# -.net
KiCad netlist of a schematic drawn in Altium Designer
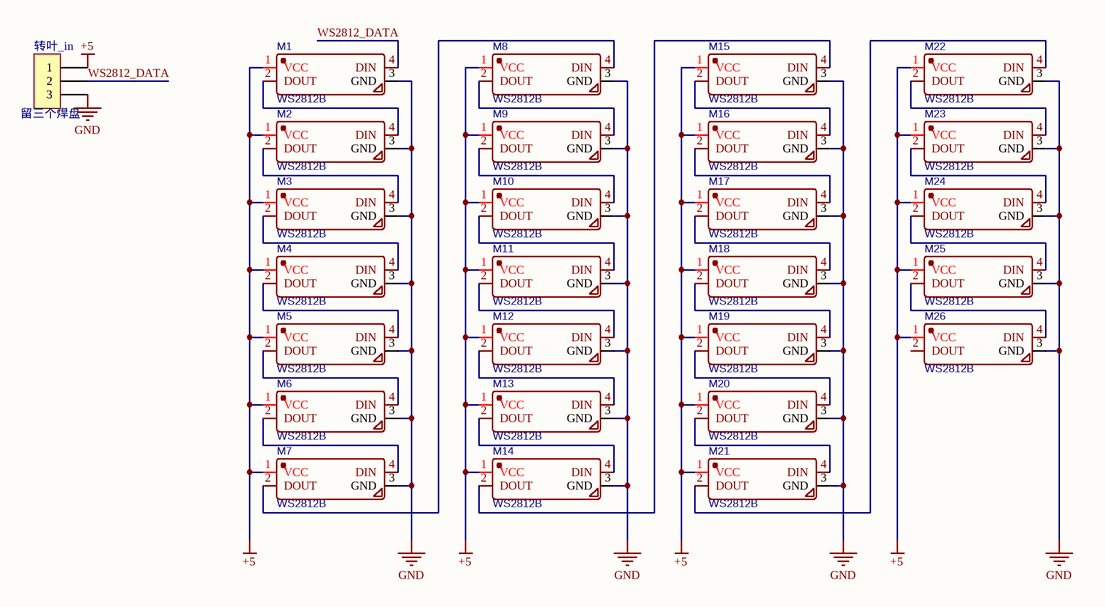
[diagram p0: 转叶板-转叶.SchDoc]

(export (version "E")
  (design (tool "Eeschema 10.0.6"))
  (components
    (comp (ref "M1")
      (value "WS2812B")
      (footprint "WS2812-NEW")
      (fields (field (name "BOM_SUPPLIER PART") "C114585") (field (name "CONTRIBUTOR") "LCSC"))
      (libsource (lib "PCB_Project") (part "WS2812B"))
    )
    (comp (ref "M2")
      (value "WS2812B")
      (footprint "WS2812-NEW")
      (fields (field (name "BOM_SUPPLIER PART") "C114585") (field (name "CONTRIBUTOR") "LCSC"))
      (libsource (lib "PCB_Project") (part "WS2812B"))
    )
    (comp (ref "M3")
      (value "WS2812B")
      (footprint "WS2812-NEW")
      (fields (field (name "BOM_SUPPLIER PART") "C114585") (field (name "CONTRIBUTOR") "LCSC"))
      (libsource (lib "PCB_Project") (part "WS2812B"))
    )
    (comp (ref "M4")
      (value "WS2812B")
      (footprint "WS2812-NEW")
      (fields (field (name "BOM_SUPPLIER PART") "C114585") (field (name "CONTRIBUTOR") "LCSC"))
      (libsource (lib "PCB_Project") (part "WS2812B"))
    )
    (comp (ref "M5")
      (value "WS2812B")
      (footprint "WS2812-NEW")
      (fields (field (name "BOM_SUPPLIER PART") "C114585") (field (name "CONTRIBUTOR") "LCSC"))
      (libsource (lib "PCB_Project") (part "WS2812B"))
    )
    (comp (ref "M6")
      (value "WS2812B")
      (footprint "WS2812-NEW")
      (fields (field (name "BOM_SUPPLIER PART") "C114585") (field (name "CONTRIBUTOR") "LCSC"))
      (libsource (lib "PCB_Project") (part "WS2812B"))
    )
    (comp (ref "M7")
      (value "WS2812B")
      (footprint "WS2812-NEW")
      (fields (field (name "BOM_SUPPLIER PART") "C114585") (field (name "CONTRIBUTOR") "LCSC"))
      (libsource (lib "PCB_Project") (part "WS2812B"))
    )
    (comp (ref "M8")
      (value "WS2812B")
      (footprint "WS2812-NEW")
      (fields (field (name "BOM_SUPPLIER PART") "C114585") (field (name "CONTRIBUTOR") "LCSC"))
      (libsource (lib "PCB_Project") (part "WS2812B"))
    )
    (comp (ref "M9")
      (value "WS2812B")
      (footprint "WS2812-NEW")
      (fields (field (name "BOM_SUPPLIER PART") "C114585") (field (name "CONTRIBUTOR") "LCSC"))
      (libsource (lib "PCB_Project") (part "WS2812B"))
    )
    (comp (ref "M10")
      (value "WS2812B")
      (footprint "WS2812-NEW")
      (fields (field (name "BOM_SUPPLIER PART") "C114585") (field (name "CONTRIBUTOR") "LCSC"))
      (libsource (lib "PCB_Project") (part "WS2812B"))
    )
    (comp (ref "M11")
      (value "WS2812B")
      (footprint "WS2812-NEW")
      (fields (field (name "BOM_SUPPLIER PART") "C114585") (field (name "CONTRIBUTOR") "LCSC"))
      (libsource (lib "PCB_Project") (part "WS2812B"))
    )
    (comp (ref "M12")
      (value "WS2812B")
      (footprint "WS2812-NEW")
      (fields (field (name "BOM_SUPPLIER PART") "C114585") (field (name "CONTRIBUTOR") "LCSC"))
      (libsource (lib "PCB_Project") (part "WS2812B"))
    )
    (comp (ref "M13")
      (value "WS2812B")
      (footprint "WS2812-NEW")
      (fields (field (name "BOM_SUPPLIER PART") "C114585") (field (name "CONTRIBUTOR") "LCSC"))
      (libsource (lib "PCB_Project") (part "WS2812B"))
    )
    (comp (ref "M14")
      (value "WS2812B")
      (footprint "WS2812-NEW")
      (fields (field (name "BOM_SUPPLIER PART") "C114585") (field (name "CONTRIBUTOR") "LCSC"))
      (libsource (lib "PCB_Project") (part "WS2812B"))
    )
    (comp (ref "M15")
      (value "WS2812B")
      (footprint "WS2812-NEW")
      (fields (field (name "BOM_SUPPLIER PART") "C114585") (field (name "CONTRIBUTOR") "LCSC"))
      (libsource (lib "PCB_Project") (part "WS2812B"))
    )
    (comp (ref "M16")
      (value "WS2812B")
      (footprint "WS2812-NEW")
      (fields (field (name "BOM_SUPPLIER PART") "C114585") (field (name "CONTRIBUTOR") "LCSC"))
      (libsource (lib "PCB_Project") (part "WS2812B"))
    )
    (comp (ref "M17")
      (value "WS2812B")
      (footprint "WS2812-NEW")
      (fields (field (name "BOM_SUPPLIER PART") "C114585") (field (name "CONTRIBUTOR") "LCSC"))
      (libsource (lib "PCB_Project") (part "WS2812B"))
    )
    (comp (ref "M18")
      (value "WS2812B")
      (footprint "WS2812-NEW")
      (fields (field (name "BOM_SUPPLIER PART") "C114585") (field (name "CONTRIBUTOR") "LCSC"))
      (libsource (lib "PCB_Project") (part "WS2812B"))
    )
    (comp (ref "M19")
      (value "WS2812B")
      (footprint "WS2812-NEW")
      (fields (field (name "BOM_SUPPLIER PART") "C114585") (field (name "CONTRIBUTOR") "LCSC"))
      (libsource (lib "PCB_Project") (part "WS2812B"))
    )
    (comp (ref "M20")
      (value "WS2812B")
      (footprint "WS2812-NEW")
      (fields (field (name "BOM_SUPPLIER PART") "C114585") (field (name "CONTRIBUTOR") "LCSC"))
      (libsource (lib "PCB_Project") (part "WS2812B"))
    )
    (comp (ref "M21")
      (value "WS2812B")
      (footprint "WS2812-NEW")
      (fields (field (name "BOM_SUPPLIER PART") "C114585") (field (name "CONTRIBUTOR") "LCSC"))
      (libsource (lib "PCB_Project") (part "WS2812B"))
    )
    (comp (ref "M22")
      (value "WS2812B")
      (footprint "WS2812-NEW")
      (fields (field (name "BOM_SUPPLIER PART") "C114585") (field (name "CONTRIBUTOR") "LCSC"))
      (libsource (lib "PCB_Project") (part "WS2812B"))
    )
    (comp (ref "M23")
      (value "WS2812B")
      (footprint "WS2812-NEW")
      (fields (field (name "BOM_SUPPLIER PART") "C114585") (field (name "CONTRIBUTOR") "LCSC"))
      (libsource (lib "PCB_Project") (part "WS2812B"))
    )
    (comp (ref "M24")
      (value "WS2812B")
      (footprint "WS2812-NEW")
      (fields (field (name "BOM_SUPPLIER PART") "C114585") (field (name "CONTRIBUTOR") "LCSC"))
      (libsource (lib "PCB_Project") (part "WS2812B"))
    )
    (comp (ref "M25")
      (value "WS2812B")
      (footprint "WS2812-NEW")
      (fields (field (name "BOM_SUPPLIER PART") "C114585") (field (name "CONTRIBUTOR") "LCSC"))
      (libsource (lib "PCB_Project") (part "WS2812B"))
    )
    (comp (ref "M26")
      (value "WS2812B")
      (footprint "WS2812-NEW")
      (fields (field (name "BOM_SUPPLIER PART") "C114585") (field (name "CONTRIBUTOR") "LCSC"))
      (libsource (lib "PCB_Project") (part "WS2812B"))
    )
    (comp (ref "转叶_in")
      (value "留三个焊盘")
      (footprint "Pin HDR1X3/2.54mm-S")
      (libsource (lib "排针") (part "Pin HDR1X3"))
    )
  )
  (nets
    (net (code "1") (name "+5") (class "Default")
      (node (ref "M1") (pin "1") (pinfunction "VCC_1") (pintype "passive"))
      (node (ref "M10") (pin "1") (pinfunction "VCC_1") (pintype "passive"))
      (node (ref "M11") (pin "1") (pinfunction "VCC_1") (pintype "passive"))
      (node (ref "M12") (pin "1") (pinfunction "VCC_1") (pintype "passive"))
      (node (ref "M13") (pin "1") (pinfunction "VCC_1") (pintype "passive"))
      (node (ref "M14") (pin "1") (pinfunction "VCC_1") (pintype "passive"))
      (node (ref "M15") (pin "1") (pinfunction "VCC_1") (pintype "passive"))
      (node (ref "M16") (pin "1") (pinfunction "VCC_1") (pintype "passive"))
      (node (ref "M17") (pin "1") (pinfunction "VCC_1") (pintype "passive"))
      (node (ref "M18") (pin "1") (pinfunction "VCC_1") (pintype "passive"))
      (node (ref "M19") (pin "1") (pinfunction "VCC_1") (pintype "passive"))
      (node (ref "M2") (pin "1") (pinfunction "VCC_1") (pintype "passive"))
      (node (ref "M20") (pin "1") (pinfunction "VCC_1") (pintype "passive"))
      (node (ref "M21") (pin "1") (pinfunction "VCC_1") (pintype "passive"))
      (node (ref "M22") (pin "1") (pinfunction "VCC_1") (pintype "passive"))
      (node (ref "M23") (pin "1") (pinfunction "VCC_1") (pintype "passive"))
      (node (ref "M24") (pin "1") (pinfunction "VCC_1") (pintype "passive"))
      (node (ref "M25") (pin "1") (pinfunction "VCC_1") (pintype "passive"))
      (node (ref "M26") (pin "1") (pinfunction "VCC_1") (pintype "passive"))
      (node (ref "M3") (pin "1") (pinfunction "VCC_1") (pintype "passive"))
      (node (ref "M4") (pin "1") (pinfunction "VCC_1") (pintype "passive"))
      (node (ref "M5") (pin "1") (pinfunction "VCC_1") (pintype "passive"))
      (node (ref "M6") (pin "1") (pinfunction "VCC_1") (pintype "passive"))
      (node (ref "M7") (pin "1") (pinfunction "VCC_1") (pintype "passive"))
      (node (ref "M8") (pin "1") (pinfunction "VCC_1") (pintype "passive"))
      (node (ref "M9") (pin "1") (pinfunction "VCC_1") (pintype "passive"))
      (node (ref "转叶_in") (pin "1") (pinfunction "1_1") (pintype "passive"))
    )
    (net (code "2") (name "/WS2812_DATA") (class "Default")
      (node (ref "M1") (pin "4") (pinfunction "DIN_4") (pintype "passive"))
      (node (ref "转叶_in") (pin "2") (pinfunction "2_2") (pintype "passive"))
    )
    (net (code "3") (name "GND") (class "Default")
      (node (ref "M1") (pin "3") (pinfunction "GND_3") (pintype "passive"))
      (node (ref "M10") (pin "3") (pinfunction "GND_3") (pintype "passive"))
      (node (ref "M11") (pin "3") (pinfunction "GND_3") (pintype "passive"))
      (node (ref "M12") (pin "3") (pinfunction "GND_3") (pintype "passive"))
      (node (ref "M13") (pin "3") (pinfunction "GND_3") (pintype "passive"))
      (node (ref "M14") (pin "3") (pinfunction "GND_3") (pintype "passive"))
      (node (ref "M15") (pin "3") (pinfunction "GND_3") (pintype "passive"))
      (node (ref "M16") (pin "3") (pinfunction "GND_3") (pintype "passive"))
      (node (ref "M17") (pin "3") (pinfunction "GND_3") (pintype "passive"))
      (node (ref "M18") (pin "3") (pinfunction "GND_3") (pintype "passive"))
      (node (ref "M19") (pin "3") (pinfunction "GND_3") (pintype "passive"))
      (node (ref "M2") (pin "3") (pinfunction "GND_3") (pintype "passive"))
      (node (ref "M20") (pin "3") (pinfunction "GND_3") (pintype "passive"))
      (node (ref "M21") (pin "3") (pinfunction "GND_3") (pintype "passive"))
      (node (ref "M22") (pin "3") (pinfunction "GND_3") (pintype "passive"))
      (node (ref "M23") (pin "3") (pinfunction "GND_3") (pintype "passive"))
      (node (ref "M24") (pin "3") (pinfunction "GND_3") (pintype "passive"))
      (node (ref "M25") (pin "3") (pinfunction "GND_3") (pintype "passive"))
      (node (ref "M26") (pin "3") (pinfunction "GND_3") (pintype "passive"))
      (node (ref "M3") (pin "3") (pinfunction "GND_3") (pintype "passive"))
      (node (ref "M4") (pin "3") (pinfunction "GND_3") (pintype "passive"))
      (node (ref "M5") (pin "3") (pinfunction "GND_3") (pintype "passive"))
      (node (ref "M6") (pin "3") (pinfunction "GND_3") (pintype "passive"))
      (node (ref "M7") (pin "3") (pinfunction "GND_3") (pintype "passive"))
      (node (ref "M8") (pin "3") (pinfunction "GND_3") (pintype "passive"))
      (node (ref "M9") (pin "3") (pinfunction "GND_3") (pintype "passive"))
      (node (ref "转叶_in") (pin "3") (pinfunction "3_3") (pintype "passive"))
    )
    (net (code "4") (name "Net-(M1-DOUT)") (class "Default")
      (node (ref "M1") (pin "2") (pinfunction "DOUT_2") (pintype "passive"))
      (node (ref "M2") (pin "4") (pinfunction "DIN_4") (pintype "passive"))
    )
    (net (code "5") (name "Net-(M2-DOUT)") (class "Default")
      (node (ref "M2") (pin "2") (pinfunction "DOUT_2") (pintype "passive"))
      (node (ref "M3") (pin "4") (pinfunction "DIN_4") (pintype "passive"))
    )
    (net (code "6") (name "Net-(M3-DOUT)") (class "Default")
      (node (ref "M3") (pin "2") (pinfunction "DOUT_2") (pintype "passive"))
      (node (ref "M4") (pin "4") (pinfunction "DIN_4") (pintype "passive"))
    )
    (net (code "7") (name "Net-(M4-DOUT)") (class "Default")
      (node (ref "M4") (pin "2") (pinfunction "DOUT_2") (pintype "passive"))
      (node (ref "M5") (pin "4") (pinfunction "DIN_4") (pintype "passive"))
    )
    (net (code "8") (name "Net-(M5-DOUT)") (class "Default")
      (node (ref "M5") (pin "2") (pinfunction "DOUT_2") (pintype "passive"))
      (node (ref "M6") (pin "4") (pinfunction "DIN_4") (pintype "passive"))
    )
    (net (code "9") (name "Net-(M6-DOUT)") (class "Default")
      (node (ref "M6") (pin "2") (pinfunction "DOUT_2") (pintype "passive"))
      (node (ref "M7") (pin "4") (pinfunction "DIN_4") (pintype "passive"))
    )
    (net (code "10") (name "Net-(M7-DOUT)") (class "Default")
      (node (ref "M7") (pin "2") (pinfunction "DOUT_2") (pintype "passive"))
      (node (ref "M8") (pin "4") (pinfunction "DIN_4") (pintype "passive"))
    )
    (net (code "11") (name "Net-(M8-DOUT)") (class "Default")
      (node (ref "M8") (pin "2") (pinfunction "DOUT_2") (pintype "passive"))
      (node (ref "M9") (pin "4") (pinfunction "DIN_4") (pintype "passive"))
    )
    (net (code "12") (name "Net-(M10-DIN)") (class "Default")
      (node (ref "M10") (pin "4") (pinfunction "DIN_4") (pintype "passive"))
      (node (ref "M9") (pin "2") (pinfunction "DOUT_2") (pintype "passive"))
    )
    (net (code "13") (name "Net-(M10-DOUT)") (class "Default")
      (node (ref "M10") (pin "2") (pinfunction "DOUT_2") (pintype "passive"))
      (node (ref "M11") (pin "4") (pinfunction "DIN_4") (pintype "passive"))
    )
    (net (code "14") (name "Net-(M11-DOUT)") (class "Default")
      (node (ref "M11") (pin "2") (pinfunction "DOUT_2") (pintype "passive"))
      (node (ref "M12") (pin "4") (pinfunction "DIN_4") (pintype "passive"))
    )
    (net (code "15") (name "Net-(M12-DOUT)") (class "Default")
      (node (ref "M12") (pin "2") (pinfunction "DOUT_2") (pintype "passive"))
      (node (ref "M13") (pin "4") (pinfunction "DIN_4") (pintype "passive"))
    )
    (net (code "16") (name "Net-(M13-DOUT)") (class "Default")
      (node (ref "M13") (pin "2") (pinfunction "DOUT_2") (pintype "passive"))
      (node (ref "M14") (pin "4") (pinfunction "DIN_4") (pintype "passive"))
    )
    (net (code "17") (name "Net-(M14-DOUT)") (class "Default")
      (node (ref "M14") (pin "2") (pinfunction "DOUT_2") (pintype "passive"))
      (node (ref "M15") (pin "4") (pinfunction "DIN_4") (pintype "passive"))
    )
    (net (code "18") (name "Net-(M15-DOUT)") (class "Default")
      (node (ref "M15") (pin "2") (pinfunction "DOUT_2") (pintype "passive"))
      (node (ref "M16") (pin "4") (pinfunction "DIN_4") (pintype "passive"))
    )
    (net (code "19") (name "Net-(M16-DOUT)") (class "Default")
      (node (ref "M16") (pin "2") (pinfunction "DOUT_2") (pintype "passive"))
      (node (ref "M17") (pin "4") (pinfunction "DIN_4") (pintype "passive"))
    )
    (net (code "20") (name "Net-(M17-DOUT)") (class "Default")
      (node (ref "M17") (pin "2") (pinfunction "DOUT_2") (pintype "passive"))
      (node (ref "M18") (pin "4") (pinfunction "DIN_4") (pintype "passive"))
    )
    (net (code "21") (name "Net-(M18-DOUT)") (class "Default")
      (node (ref "M18") (pin "2") (pinfunction "DOUT_2") (pintype "passive"))
      (node (ref "M19") (pin "4") (pinfunction "DIN_4") (pintype "passive"))
    )
    (net (code "22") (name "Net-(M19-DOUT)") (class "Default")
      (node (ref "M19") (pin "2") (pinfunction "DOUT_2") (pintype "passive"))
      (node (ref "M20") (pin "4") (pinfunction "DIN_4") (pintype "passive"))
    )
    (net (code "23") (name "Net-(M20-DOUT)") (class "Default")
      (node (ref "M20") (pin "2") (pinfunction "DOUT_2") (pintype "passive"))
      (node (ref "M21") (pin "4") (pinfunction "DIN_4") (pintype "passive"))
    )
    (net (code "24") (name "Net-(M21-DOUT)") (class "Default")
      (node (ref "M21") (pin "2") (pinfunction "DOUT_2") (pintype "passive"))
      (node (ref "M22") (pin "4") (pinfunction "DIN_4") (pintype "passive"))
    )
    (net (code "25") (name "Net-(M22-DOUT)") (class "Default")
      (node (ref "M22") (pin "2") (pinfunction "DOUT_2") (pintype "passive"))
      (node (ref "M23") (pin "4") (pinfunction "DIN_4") (pintype "passive"))
    )
    (net (code "26") (name "Net-(M23-DOUT)") (class "Default")
      (node (ref "M23") (pin "2") (pinfunction "DOUT_2") (pintype "passive"))
      (node (ref "M24") (pin "4") (pinfunction "DIN_4") (pintype "passive"))
    )
    (net (code "27") (name "Net-(M24-DOUT)") (class "Default")
      (node (ref "M24") (pin "2") (pinfunction "DOUT_2") (pintype "passive"))
      (node (ref "M25") (pin "4") (pinfunction "DIN_4") (pintype "passive"))
    )
    (net (code "28") (name "Net-(M25-DOUT)") (class "Default")
      (node (ref "M25") (pin "2") (pinfunction "DOUT_2") (pintype "passive"))
      (node (ref "M26") (pin "4") (pinfunction "DIN_4") (pintype "passive"))
    )
    (net (code "29") (name "unconnected-(M26-DOUT-Pad2)") (class "Default")
      (node (ref "M26") (pin "2") (pinfunction "DOUT_2") (pintype "passive"))
    )
  )
)
